# ST_Link.net
KiCad netlist of a schematic drawn in Altium Designer
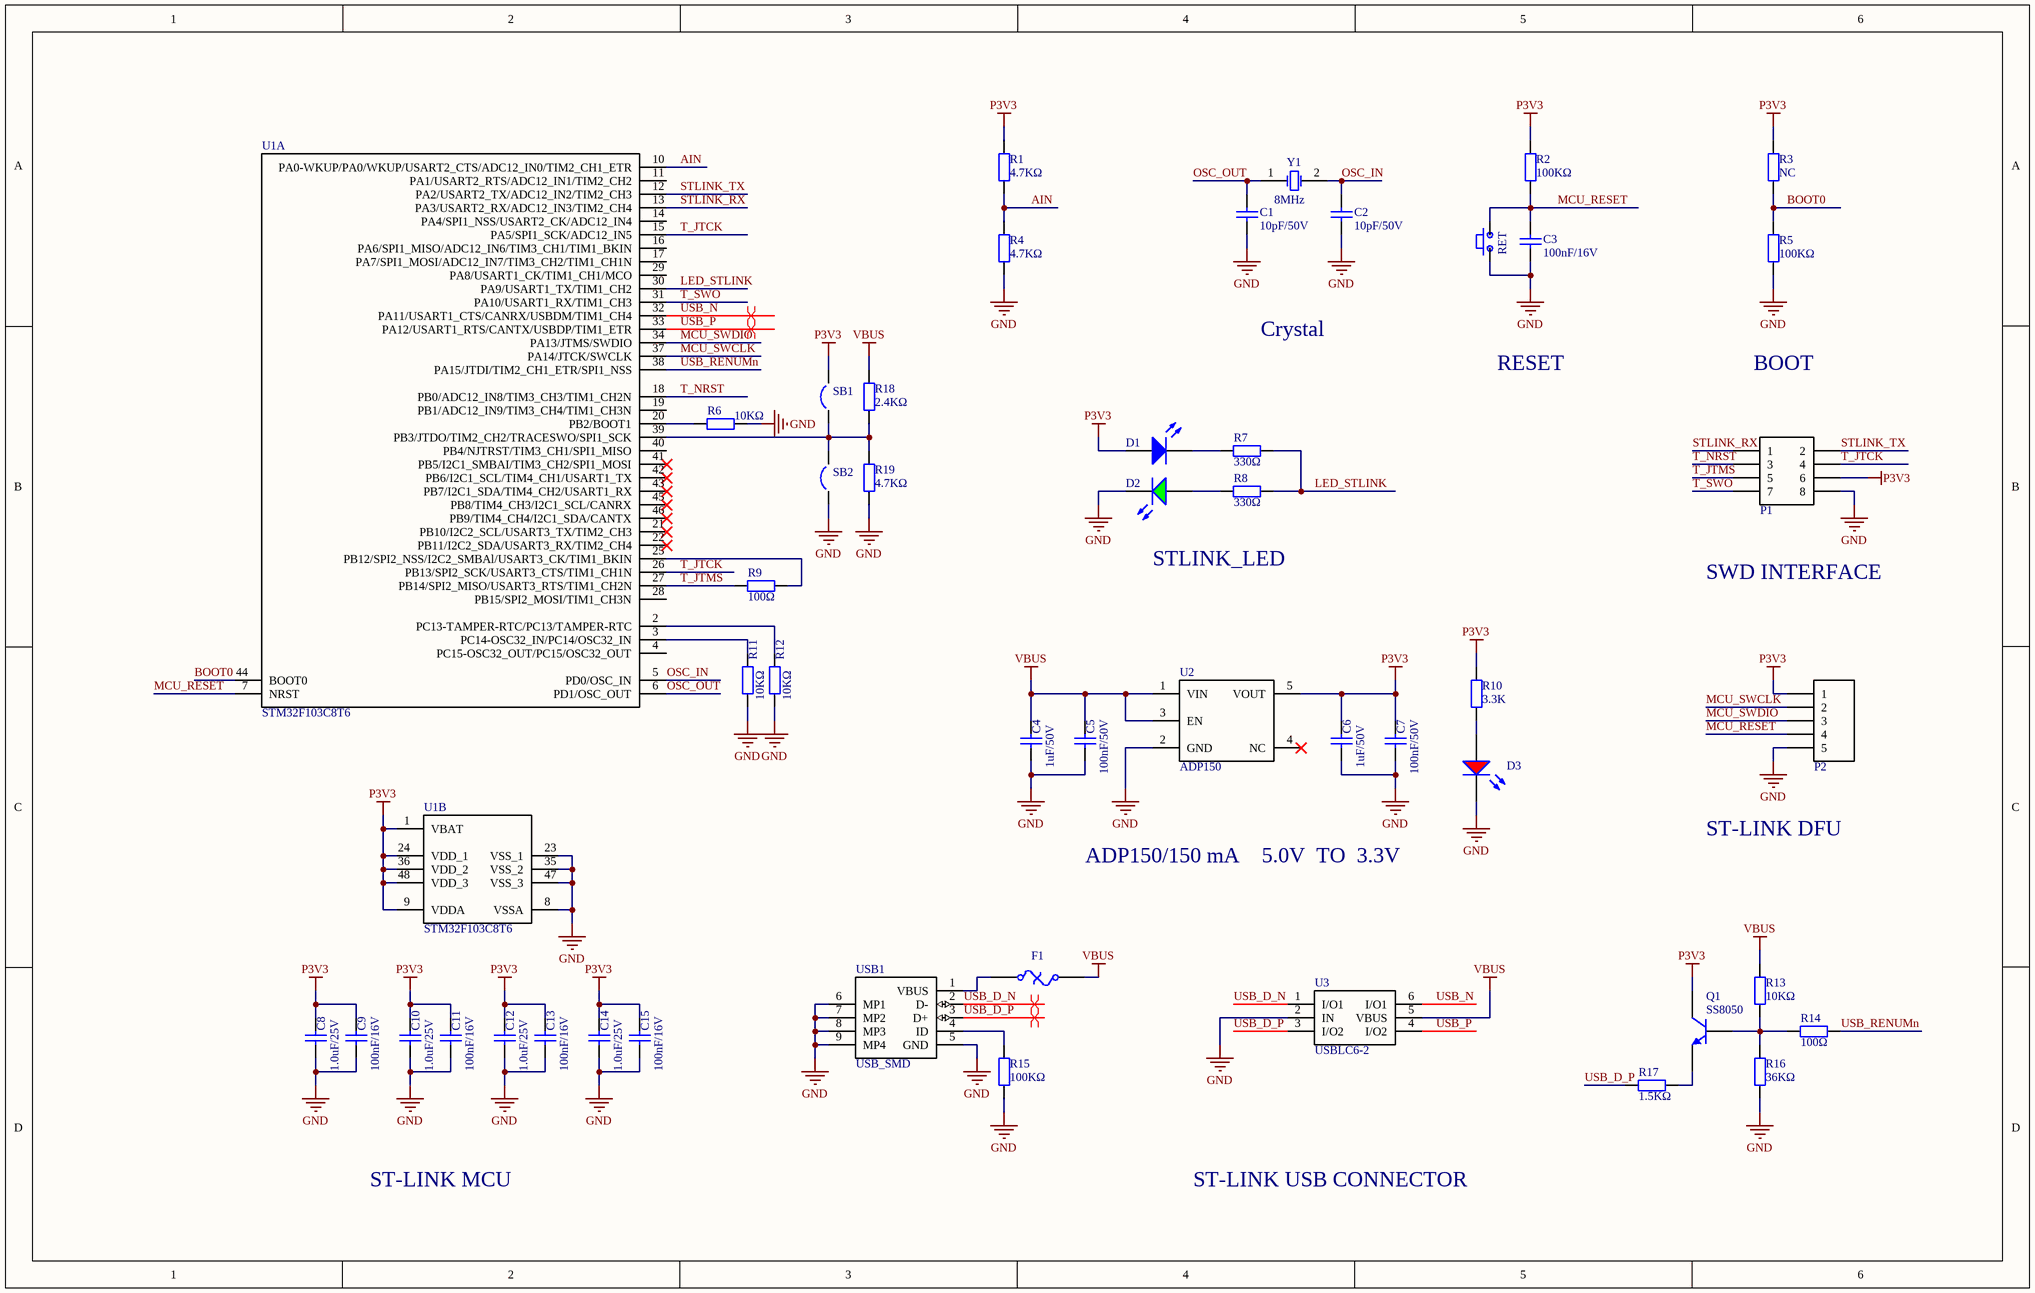
[diagram p0: ST_Link.SchDoc]

(export (version "E")
  (design (tool "Eeschema 10.0.6"))
  (components
    (comp (ref "C1")
      (value "10pF/50V")
      (footprint "0402_C")
      (description "贴片电容")
      (libsource (lib "Miscellaneous Devices LC") (part "0402 10pF (100) 5% 50V"))
    )
    (comp (ref "C2")
      (value "10pF/50V")
      (footprint "0402_C")
      (description "贴片电容")
      (libsource (lib "Miscellaneous Devices LC") (part "0402 10pF (100) 5% 50V"))
    )
    (comp (ref "C3")
      (value "100nF/16V")
      (footprint "0402_C")
      (description "贴片电容")
      (libsource (lib "Miscellaneous Devices LC") (part "0402 100nF (104) 10% 16V"))
    )
    (comp (ref "C4")
      (value "1uF/50V")
      (footprint "0603_C")
      (description "贴片电容")
      (libsource (lib "Miscellaneous Devices LC") (part "0603 1uF (105) 10% 50V"))
    )
    (comp (ref "C5")
      (value "100nF/50V")
      (footprint "0603_C")
      (description "贴片电容")
      (libsource (lib "Miscellaneous Devices LC") (part "0603 100nF (104) 10% 50V"))
    )
    (comp (ref "C6")
      (value "1uF/50V")
      (footprint "0603_C")
      (description "贴片电容")
      (libsource (lib "Miscellaneous Devices LC") (part "0603 1uF (105) 10% 50V"))
    )
    (comp (ref "C7")
      (value "100nF/50V")
      (footprint "0603_C")
      (description "贴片电容")
      (libsource (lib "Miscellaneous Devices LC") (part "0603 100nF (104) 10% 50V"))
    )
    (comp (ref "C8")
      (value "1.0uF/25V")
      (footprint "0402_C")
      (description "贴片电容")
      (libsource (lib "Miscellaneous Devices LC") (part "0402 1.0uF (105) 10% 25V"))
    )
    (comp (ref "C9")
      (value "100nF/16V")
      (footprint "0402_C")
      (description "贴片电容")
      (libsource (lib "Miscellaneous Devices LC") (part "0402 100nF (104) 10% 16V"))
    )
    (comp (ref "C10")
      (value "1.0uF/25V")
      (footprint "0402_C")
      (description "贴片电容")
      (libsource (lib "Miscellaneous Devices LC") (part "0402 1.0uF (105) 10% 25V"))
    )
    (comp (ref "C11")
      (value "100nF/16V")
      (footprint "0402_C")
      (description "贴片电容")
      (libsource (lib "Miscellaneous Devices LC") (part "0402 100nF (104) 10% 16V"))
    )
    (comp (ref "C12")
      (value "1.0uF/25V")
      (footprint "0402_C")
      (description "贴片电容")
      (libsource (lib "Miscellaneous Devices LC") (part "0402 1.0uF (105) 10% 25V"))
    )
    (comp (ref "C13")
      (value "100nF/16V")
      (footprint "0402_C")
      (description "贴片电容")
      (libsource (lib "Miscellaneous Devices LC") (part "0402 100nF (104) 10% 16V"))
    )
    (comp (ref "C14")
      (value "1.0uF/25V")
      (footprint "0402_C")
      (description "贴片电容")
      (libsource (lib "Miscellaneous Devices LC") (part "0402 1.0uF (105) 10% 25V"))
    )
    (comp (ref "C15")
      (value "100nF/16V")
      (footprint "0402_C")
      (description "贴片电容")
      (libsource (lib "Miscellaneous Devices LC") (part "0402 100nF (104) 10% 16V"))
    )
    (comp (ref "D1")
      (value "~")
      (footprint "0603_LED_S1")
      (description "发光二极管")
      (libsource (lib "Miscellaneous Devices LC") (part "0603 蓝灯"))
    )
    (comp (ref "D2")
      (value "~")
      (footprint "0603_LED_S1")
      (description "发光二极管")
      (libsource (lib "Miscellaneous Devices LC") (part "0603 绿灯"))
    )
    (comp (ref "D3")
      (value "红灯 0603")
      (footprint "0603_LED_S1")
      (description "发光二极管")
      (libsource (lib "Miscellaneous Devices LC") (part "0603 红灯"))
    )
    (comp (ref "F1")
      (value "500mA")
      (footprint "F1206")
      (description "Fuse")
      (libsource (lib "Discrete") (part "Fuse"))
    )
    (comp (ref "P1")
      (value "Header")
      (footprint "SMT 2*4 2.54")
      (description "Header, 4-Pin, Dual row")
      (fields (field (name "PUBLISHER") "Altium Limited"))
      (libsource (lib "Connectors") (part "Header 4X2"))
    )
    (comp (ref "P2")
      (value "Header 5")
      (footprint "DIP5_2.00")
      (description "Header, 5-Pin")
      (libsource (lib "Connectors") (part "Header 5"))
    )
    (comp (ref "Q1")
      (value "SS8050")
      (footprint "SOT-23(SOT-23-3)")
      (description "三极管")
      (libsource (lib "Miscellaneous Devices LC") (part "SOT-23 SS8050 Y1"))
    )
    (comp (ref "R1")
      (value "4.7KΩ")
      (footprint "0402_R")
      (description "贴片电阻")
      (libsource (lib "Miscellaneous Devices LC") (part "0402 4.7KΩ (4701) 1%"))
    )
    (comp (ref "R2")
      (value "100KΩ")
      (footprint "0402_R")
      (description "贴片电阻")
      (libsource (lib "Miscellaneous Devices LC") (part "0402 100KΩ (1003) 1%"))
    )
    (comp (ref "R3")
      (value "NC")
      (footprint "0402_R")
      (description "贴片电阻")
      (libsource (lib "Miscellaneous Devices LC") (part "0402 10KΩ (1002) 1%"))
    )
    (comp (ref "R4")
      (value "4.7KΩ")
      (footprint "0402_R")
      (description "贴片电阻")
      (libsource (lib "Miscellaneous Devices LC") (part "0402 4.7KΩ (4701) 1%"))
    )
    (comp (ref "R5")
      (value "100KΩ")
      (footprint "0402_R")
      (description "贴片电阻")
      (libsource (lib "Miscellaneous Devices LC") (part "0402 100KΩ (1003) 1%"))
    )
    (comp (ref "R6")
      (value "10KΩ")
      (footprint "0402_R")
      (description "贴片电阻")
      (libsource (lib "") (part "0402 10KΩ (1002) 1%_1"))
    )
    (comp (ref "R7")
      (value "330Ω")
      (footprint "0402_R")
      (description "贴片电阻")
      (libsource (lib "Miscellaneous Devices LC") (part "0402 330Ω (3300) 1%"))
    )
    (comp (ref "R8")
      (value "330Ω")
      (footprint "0402_R")
      (description "贴片电阻")
      (libsource (lib "Miscellaneous Devices LC") (part "0402 330Ω (3300) 1%"))
    )
    (comp (ref "R9")
      (value "100Ω")
      (footprint "0402_R")
      (description "贴片电阻")
      (libsource (lib "Miscellaneous Devices LC") (part "0402 100Ω (1000) 1%"))
    )
    (comp (ref "R10")
      (value "3.3K")
      (footprint "0603_R")
      (description "贴片电阻")
      (libsource (lib "Miscellaneous Devices LC") (part "0603 3.3KΩ (3301) 1%"))
    )
    (comp (ref "R11")
      (value "10KΩ")
      (footprint "0402_R")
      (description "贴片电阻")
      (libsource (lib "Miscellaneous Devices LC") (part "0402 10KΩ (1002) 1%"))
    )
    (comp (ref "R12")
      (value "10KΩ")
      (footprint "0402_R")
      (description "贴片电阻")
      (libsource (lib "Miscellaneous Devices LC") (part "0402 10KΩ (1002) 1%"))
    )
    (comp (ref "R13")
      (value "10KΩ")
      (footprint "0402_R")
      (description "贴片电阻")
      (libsource (lib "Miscellaneous Devices LC") (part "0402 10KΩ (1002) 1%"))
    )
    (comp (ref "R14")
      (value "100Ω")
      (footprint "0402_R")
      (description "贴片电阻")
      (libsource (lib "Miscellaneous Devices LC") (part "0402 100Ω (1000) 1%"))
    )
    (comp (ref "R15")
      (value "100KΩ")
      (footprint "0402_R")
      (description "贴片电阻")
      (libsource (lib "Miscellaneous Devices LC") (part "0402 100KΩ (1003) 1%"))
    )
    (comp (ref "R16")
      (value "36KΩ")
      (footprint "0402_R")
      (description "贴片电阻")
      (libsource (lib "Miscellaneous Devices LC") (part "0402 39KΩ (3902) 1%"))
    )
    (comp (ref "R17")
      (value "1.5KΩ")
      (footprint "0402_R")
      (description "贴片电阻")
      (libsource (lib "Miscellaneous Devices LC") (part "0402 1.5KΩ (1501) 1%"))
    )
    (comp (ref "R18")
      (value "2.4KΩ")
      (footprint "0402_R")
      (description "贴片电阻")
      (libsource (lib "Miscellaneous Devices LC") (part "0402 2.4KΩ (2401) 1%"))
    )
    (comp (ref "R19")
      (value "4.7KΩ")
      (footprint "0402_R")
      (description "贴片电阻")
      (libsource (lib "Miscellaneous Devices LC") (part "0402 4.7KΩ (4701) 1%"))
    )
    (comp (ref "RET")
      (value "Button")
      (footprint "SKRKAHE020")
      (libsource (lib "Connectors") (part "Button"))
    )
    (comp (ref "SB1") (value "SB") (footprint "SB") (libsource (lib "Connectors") (part "SB")))
    (comp (ref "SB2") (value "SB") (footprint "SB") (libsource (lib "") (part "SB_1")))
    (comp (ref "U1")
      (value "STM32F103C8T6")
      (footprint "LQFP-48")
      (libsource (lib "IC") (part "STM32F103C8T6"))
    )
    (comp (ref "U2")
      (value "ADP150")
      (footprint "SOT23-5")
      (description "Ultralow Noise,150 mA CMOS Linear Regulator")
      (libsource (lib "IC") (part "ADP150"))
    )
    (comp (ref "U3")
      (value "USBLC6-2")
      (footprint "SOT23-6")
      (description "Very low capacitance ESD protection")
      (libsource (lib "IC") (part "USBLC6-2"))
    )
    (comp (ref "USB1")
      (value "USB_SMD")
      (footprint "USB_Micro")
      (libsource (lib "Connectors") (part "USB_SMD"))
    )
    (comp (ref "Y1")
      (value "8MHz")
      (footprint "SMD-5032_2P")
      (description "贴片晶振")
      (libsource (lib "Miscellaneous Devices LC") (part "SMD-5032_2P 8MHz 20ppm 20pF"))
    )
  )
  (nets
    (net (code "1") (name "/AIN") (class "Default")
      (node (ref "R1") (pin "1") (pinfunction "1_1") (pintype "passive"))
      (node (ref "R4") (pin "2") (pinfunction "2_2") (pintype "passive"))
      (node (ref "U1") (pin "10") (pinfunction "PA0-WKUP/PA0/WKUP/USART2_CTS/ADC12_IN0/TIM2_CH1_ETR_10") (pintype "passive"))
    )
    (net (code "2") (name "/BOOT0") (class "Default")
      (node (ref "R3") (pin "1") (pinfunction "1_1") (pintype "passive"))
      (node (ref "R5") (pin "2") (pinfunction "2_2") (pintype "passive"))
      (node (ref "U1") (pin "44") (pinfunction "BOOT0_44") (pintype "passive"))
    )
    (net (code "3") (name "/LED_STLINK") (class "Default")
      (node (ref "R7") (pin "2") (pinfunction "2_2") (pintype "passive"))
      (node (ref "R8") (pin "2") (pinfunction "2_2") (pintype "passive"))
      (node (ref "U1") (pin "30") (pinfunction "PA9/USART1_TX/TIM1_CH2_30") (pintype "passive"))
    )
    (net (code "4") (name "/MCU_RESET") (class "Default")
      (node (ref "C3") (pin "2") (pinfunction "2_2") (pintype "passive"))
      (node (ref "P2") (pin "4") (pinfunction "4_4") (pintype "passive"))
      (node (ref "R2") (pin "1") (pinfunction "1_1") (pintype "passive"))
      (node (ref "RET") (pin "2") (pinfunction "2_2") (pintype "passive"))
      (node (ref "U1") (pin "7") (pinfunction "NRST_7") (pintype "passive"))
    )
    (net (code "5") (name "/MCU_SWCLK") (class "Default")
      (node (ref "P2") (pin "2") (pinfunction "2_2") (pintype "passive"))
      (node (ref "U1") (pin "37") (pinfunction "PA14/JTCK/SWCLK_37") (pintype "passive"))
    )
    (net (code "6") (name "/MCU_SWDIO") (class "Default")
      (node (ref "P2") (pin "3") (pinfunction "3_3") (pintype "passive"))
      (node (ref "U1") (pin "34") (pinfunction "PA13/JTMS/SWDIO_34") (pintype "passive"))
    )
    (net (code "7") (name "/OSC_IN") (class "Default")
      (node (ref "C2") (pin "2") (pinfunction "2_2") (pintype "passive"))
      (node (ref "U1") (pin "5") (pinfunction "PD0/OSC_IN_5") (pintype "passive"))
      (node (ref "Y1") (pin "2") (pinfunction "OSC2_2") (pintype "passive"))
    )
    (net (code "8") (name "/OSC_OUT") (class "Default")
      (node (ref "C1") (pin "2") (pinfunction "2_2") (pintype "passive"))
      (node (ref "U1") (pin "6") (pinfunction "PD1/OSC_OUT_6") (pintype "passive"))
      (node (ref "Y1") (pin "1") (pinfunction "OSC1_1") (pintype "passive"))
    )
    (net (code "9") (name "/STLINK_RX") (class "Default")
      (node (ref "P1") (pin "1") (pinfunction "1_1") (pintype "passive"))
      (node (ref "U1") (pin "13") (pinfunction "PA3/USART2_RX/ADC12_IN3/TIM2_CH4_13") (pintype "passive"))
    )
    (net (code "10") (name "/STLINK_TX") (class "Default")
      (node (ref "P1") (pin "2") (pinfunction "2_2") (pintype "passive"))
      (node (ref "U1") (pin "12") (pinfunction "PA2/USART2_TX/ADC12_IN2/TIM2_CH3_12") (pintype "passive"))
    )
    (net (code "11") (name "/T_JTCK") (class "Default")
      (node (ref "P1") (pin "4") (pinfunction "4_4") (pintype "passive"))
      (node (ref "U1") (pin "15") (pinfunction "PA5/SPI1_SCK/ADC12_IN5_15") (pintype "passive"))
      (node (ref "U1") (pin "26") (pinfunction "PB13/SPI2_SCK/USART3_CTS/TIM1_CH1N_26") (pintype "passive"))
    )
    (net (code "12") (name "/T_JTMS") (class "Default")
      (node (ref "P1") (pin "5") (pinfunction "5_5") (pintype "passive"))
      (node (ref "R9") (pin "1") (pinfunction "1_1") (pintype "passive"))
      (node (ref "U1") (pin "27") (pinfunction "PB14/SPI2_MISO/USART3_RTS/TIM1_CH2N_27") (pintype "passive"))
    )
    (net (code "13") (name "/T_NRST") (class "Default")
      (node (ref "P1") (pin "3") (pinfunction "3_3") (pintype "passive"))
      (node (ref "U1") (pin "18") (pinfunction "PB0/ADC12_IN8/TIM3_CH3/TIM1_CH2N_18") (pintype "passive"))
    )
    (net (code "14") (name "/T_SWO") (class "Default")
      (node (ref "P1") (pin "7") (pinfunction "7_7") (pintype "passive"))
      (node (ref "U1") (pin "31") (pinfunction "PA10/USART1_RX/TIM1_CH3_31") (pintype "passive"))
    )
    (net (code "15") (name "/USB_D_N") (class "Default")
      (node (ref "U3") (pin "1") (pinfunction "I/O1_1") (pintype "passive"))
      (node (ref "USB1") (pin "2") (pinfunction "D-_2") (pintype "bidirectional"))
    )
    (net (code "16") (name "/USB_D_P") (class "Default")
      (node (ref "R17") (pin "1") (pinfunction "1_1") (pintype "passive"))
      (node (ref "U3") (pin "3") (pinfunction "I/O2_3") (pintype "passive"))
      (node (ref "USB1") (pin "3") (pinfunction "D+_3") (pintype "bidirectional"))
    )
    (net (code "17") (name "/USB_N") (class "Default")
      (node (ref "U1") (pin "32") (pinfunction "PA11/USART1_CTS/CANRX/USBDM/TIM1_CH4_32") (pintype "passive"))
      (node (ref "U3") (pin "6") (pinfunction "I/O1_6") (pintype "passive"))
    )
    (net (code "18") (name "/USB_P") (class "Default")
      (node (ref "U1") (pin "33") (pinfunction "PA12/USART1_RTS/CANTX/USBDP/TIM1_ETR_33") (pintype "passive"))
      (node (ref "U3") (pin "4") (pinfunction "I/O2_4") (pintype "passive"))
    )
    (net (code "19") (name "/USB_RENUMn") (class "Default")
      (node (ref "R14") (pin "2") (pinfunction "2_2") (pintype "passive"))
      (node (ref "U1") (pin "38") (pinfunction "PA15/JTDI/TIM2_CH1_ETR/SPI1_NSS_38") (pintype "passive"))
    )
    (net (code "20") (name "GND") (class "Default")
      (node (ref "C1") (pin "1") (pinfunction "1_1") (pintype "passive"))
      (node (ref "C10") (pin "1") (pinfunction "1_1") (pintype "passive"))
      (node (ref "C11") (pin "1") (pinfunction "1_1") (pintype "passive"))
      (node (ref "C12") (pin "1") (pinfunction "1_1") (pintype "passive"))
      (node (ref "C13") (pin "1") (pinfunction "1_1") (pintype "passive"))
      (node (ref "C14") (pin "1") (pinfunction "1_1") (pintype "passive"))
      (node (ref "C15") (pin "1") (pinfunction "1_1") (pintype "passive"))
      (node (ref "C2") (pin "1") (pinfunction "1_1") (pintype "passive"))
      (node (ref "C3") (pin "1") (pinfunction "1_1") (pintype "passive"))
      (node (ref "C4") (pin "1") (pinfunction "1_1") (pintype "passive"))
      (node (ref "C5") (pin "1") (pinfunction "1_1") (pintype "passive"))
      (node (ref "C6") (pin "1") (pinfunction "1_1") (pintype "passive"))
      (node (ref "C7") (pin "1") (pinfunction "1_1") (pintype "passive"))
      (node (ref "C8") (pin "1") (pinfunction "1_1") (pintype "passive"))
      (node (ref "C9") (pin "1") (pinfunction "1_1") (pintype "passive"))
      (node (ref "D2") (pin "K") (pinfunction "K_K") (pintype "passive"))
      (node (ref "D3") (pin "K") (pinfunction "K_K") (pintype "passive"))
      (node (ref "P1") (pin "8") (pinfunction "8_8") (pintype "passive"))
      (node (ref "P2") (pin "5") (pinfunction "5_5") (pintype "passive"))
      (node (ref "R11") (pin "1") (pinfunction "1_1") (pintype "passive"))
      (node (ref "R12") (pin "1") (pinfunction "1_1") (pintype "passive"))
      (node (ref "R15") (pin "1") (pinfunction "1_1") (pintype "passive"))
      (node (ref "R16") (pin "1") (pinfunction "1_1") (pintype "passive"))
      (node (ref "R19") (pin "1") (pinfunction "1_1") (pintype "passive"))
      (node (ref "R4") (pin "1") (pinfunction "1_1") (pintype "passive"))
      (node (ref "R5") (pin "1") (pinfunction "1_1") (pintype "passive"))
      (node (ref "R6") (pin "1") (pinfunction "1_1") (pintype "passive"))
      (node (ref "RET") (pin "1") (pinfunction "1_1") (pintype "passive"))
      (node (ref "SB2") (pin "2") (pinfunction "2_2") (pintype "passive"))
      (node (ref "U1") (pin "23") (pinfunction "VSS_1_23") (pintype "power_in"))
      (node (ref "U1") (pin "35") (pinfunction "VSS_2_35") (pintype "power_in"))
      (node (ref "U1") (pin "47") (pinfunction "VSS_3_47") (pintype "power_in"))
      (node (ref "U1") (pin "8") (pinfunction "VSSA_8") (pintype "power_in"))
      (node (ref "U2") (pin "2") (pinfunction "GND_2") (pintype "passive"))
      (node (ref "U3") (pin "2") (pinfunction "IN_2") (pintype "passive"))
      (node (ref "USB1") (pin "5") (pinfunction "GND_5") (pintype "power_in"))
      (node (ref "USB1") (pin "6") (pinfunction "MP1_6") (pintype "passive"))
      (node (ref "USB1") (pin "7") (pinfunction "MP2_7") (pintype "passive"))
      (node (ref "USB1") (pin "8") (pinfunction "MP3_8") (pintype "passive"))
      (node (ref "USB1") (pin "9") (pinfunction "MP4_9") (pintype "passive"))
    )
    (net (code "21") (name "Net-(D1-PadK)") (class "Default")
      (node (ref "D1") (pin "K") (pinfunction "K_K") (pintype "passive"))
      (node (ref "R7") (pin "1") (pinfunction "1_1") (pintype "passive"))
    )
    (net (code "22") (name "Net-(D2-PadA)") (class "Default")
      (node (ref "D2") (pin "A") (pinfunction "A_A") (pintype "passive"))
      (node (ref "R8") (pin "1") (pinfunction "1_1") (pintype "passive"))
    )
    (net (code "23") (name "Net-(D3-PadA)") (class "Default")
      (node (ref "D3") (pin "A") (pinfunction "A_A") (pintype "passive"))
      (node (ref "R10") (pin "1") (pinfunction "1_1") (pintype "passive"))
    )
    (net (code "24") (name "Net-(Q1-B)") (class "Default")
      (node (ref "Q1") (pin "1") (pinfunction "B_1") (pintype "passive"))
      (node (ref "R13") (pin "1") (pinfunction "1_1") (pintype "passive"))
      (node (ref "R14") (pin "1") (pinfunction "1_1") (pintype "passive"))
      (node (ref "R16") (pin "2") (pinfunction "2_2") (pintype "passive"))
    )
    (net (code "25") (name "Net-(Q1-E)") (class "Default")
      (node (ref "Q1") (pin "2") (pinfunction "E_2") (pintype "passive"))
      (node (ref "R17") (pin "2") (pinfunction "2_2") (pintype "passive"))
    )
    (net (code "26") (name "Net-(U1A-PB2{slash}BOOT1)") (class "Default")
      (node (ref "R6") (pin "2") (pinfunction "2_2") (pintype "passive"))
      (node (ref "U1") (pin "20") (pinfunction "PB2/BOOT1_20") (pintype "passive"))
    )
    (net (code "27") (name "Net-(U1A-PB3{slash}JTDO{slash}TIM2_CH2{slash}TRACESWO{slash}SPI1_SCK)") (class "Default")
      (node (ref "R18") (pin "1") (pinfunction "1_1") (pintype "passive"))
      (node (ref "R19") (pin "2") (pinfunction "2_2") (pintype "passive"))
      (node (ref "SB1") (pin "1") (pinfunction "1_1") (pintype "passive"))
      (node (ref "SB2") (pin "1") (pinfunction "1_1") (pintype "passive"))
      (node (ref "U1") (pin "39") (pinfunction "PB3/JTDO/TIM2_CH2/TRACESWO/SPI1_SCK_39") (pintype "passive"))
    )
    (net (code "28") (name "Net-(U1A-PB12{slash}SPI2_NSS{slash}I2C2_SMBAl{slash}USART3_CK{slash}TIM1_BKIN)") (class "Default")
      (node (ref "R9") (pin "2") (pinfunction "2_2") (pintype "passive"))
      (node (ref "U1") (pin "25") (pinfunction "PB12/SPI2_NSS/I2C2_SMBAl/USART3_CK/TIM1_BKIN_25") (pintype "passive"))
    )
    (net (code "29") (name "Net-(U1A-PC13-TAMPER-RTC{slash}PC13{slash}TAMPER-RTC)") (class "Default")
      (node (ref "R12") (pin "2") (pinfunction "2_2") (pintype "passive"))
      (node (ref "U1") (pin "2") (pinfunction "PC13-TAMPER-RTC/PC13/TAMPER-RTC_2") (pintype "passive"))
    )
    (net (code "30") (name "Net-(U1A-PC14-OSC32_IN{slash}PC14{slash}OSC32_IN)") (class "Default")
      (node (ref "R11") (pin "2") (pinfunction "2_2") (pintype "passive"))
      (node (ref "U1") (pin "3") (pinfunction "PC14-OSC32_IN/PC14/OSC32_IN_3") (pintype "passive"))
    )
    (net (code "31") (name "Net-(USB1-ID)") (class "Default")
      (node (ref "R15") (pin "2") (pinfunction "2_2") (pintype "passive"))
      (node (ref "USB1") (pin "4") (pinfunction "ID_4") (pintype "passive"))
    )
    (net (code "32") (name "Net-(USB1-VBUS)") (class "Default")
      (node (ref "F1") (pin "1") (pinfunction "1_1") (pintype "passive"))
      (node (ref "USB1") (pin "1") (pinfunction "VBUS_1") (pintype "power_in"))
    )
    (net (code "33") (name "P3V3") (class "Default")
      (node (ref "C10") (pin "2") (pinfunction "2_2") (pintype "passive"))
      (node (ref "C11") (pin "2") (pinfunction "2_2") (pintype "passive"))
      (node (ref "C12") (pin "2") (pinfunction "2_2") (pintype "passive"))
      (node (ref "C13") (pin "2") (pinfunction "2_2") (pintype "passive"))
      (node (ref "C14") (pin "2") (pinfunction "2_2") (pintype "passive"))
      (node (ref "C15") (pin "2") (pinfunction "2_2") (pintype "passive"))
      (node (ref "C6") (pin "2") (pinfunction "2_2") (pintype "passive"))
      (node (ref "C7") (pin "2") (pinfunction "2_2") (pintype "passive"))
      (node (ref "C8") (pin "2") (pinfunction "2_2") (pintype "passive"))
      (node (ref "C9") (pin "2") (pinfunction "2_2") (pintype "passive"))
      (node (ref "D1") (pin "A") (pinfunction "A_A") (pintype "passive"))
      (node (ref "P1") (pin "6") (pinfunction "6_6") (pintype "passive"))
      (node (ref "P2") (pin "1") (pinfunction "1_1") (pintype "passive"))
      (node (ref "Q1") (pin "3") (pinfunction "C_3") (pintype "passive"))
      (node (ref "R1") (pin "2") (pinfunction "2_2") (pintype "passive"))
      (node (ref "R10") (pin "2") (pinfunction "2_2") (pintype "passive"))
      (node (ref "R2") (pin "2") (pinfunction "2_2") (pintype "passive"))
      (node (ref "R3") (pin "2") (pinfunction "2_2") (pintype "passive"))
      (node (ref "SB1") (pin "2") (pinfunction "2_2") (pintype "passive"))
      (node (ref "U1") (pin "1") (pinfunction "VBAT_1") (pintype "power_in"))
      (node (ref "U1") (pin "24") (pinfunction "VDD_1_24") (pintype "power_in"))
      (node (ref "U1") (pin "36") (pinfunction "VDD_2_36") (pintype "power_in"))
      (node (ref "U1") (pin "48") (pinfunction "VDD_3_48") (pintype "power_in"))
      (node (ref "U1") (pin "9") (pinfunction "VDDA_9") (pintype "power_in"))
      (node (ref "U2") (pin "5") (pinfunction "VOUT_5") (pintype "passive"))
    )
    (net (code "34") (name "VBUS") (class "Default")
      (node (ref "C4") (pin "2") (pinfunction "2_2") (pintype "passive"))
      (node (ref "C5") (pin "2") (pinfunction "2_2") (pintype "passive"))
      (node (ref "F1") (pin "2") (pinfunction "2_2") (pintype "passive"))
      (node (ref "R13") (pin "2") (pinfunction "2_2") (pintype "passive"))
      (node (ref "R18") (pin "2") (pinfunction "2_2") (pintype "passive"))
      (node (ref "U2") (pin "1") (pinfunction "VIN_1") (pintype "passive"))
      (node (ref "U2") (pin "3") (pinfunction "EN_3") (pintype "passive"))
      (node (ref "U3") (pin "5") (pinfunction "VBUS_5") (pintype "passive"))
    )
    (net (code "35") (name "unconnected-(U1A-PA1{slash}USART2_RTS{slash}ADC12_IN1{slash}TIM2_CH2-Pad11)") (class "Default")
      (node (ref "U1") (pin "11") (pinfunction "PA1/USART2_RTS/ADC12_IN1/TIM2_CH2_11") (pintype "passive"))
    )
    (net (code "36") (name "unconnected-(U1A-PA4{slash}SPI1_NSS{slash}USART2_CK{slash}ADC12_IN4-Pad14)") (class "Default")
      (node (ref "U1") (pin "14") (pinfunction "PA4/SPI1_NSS/USART2_CK/ADC12_IN4_14") (pintype "passive"))
    )
    (net (code "37") (name "unconnected-(U1A-PA6{slash}SPI1_MISO{slash}ADC12_IN6{slash}TIM3_CH1{slash}TIM1_BKIN-Pad16)") (class "Default")
      (node (ref "U1") (pin "16") (pinfunction "PA6/SPI1_MISO/ADC12_IN6/TIM3_CH1/TIM1_BKIN_16") (pintype "passive"))
    )
    (net (code "38") (name "unconnected-(U1A-PA7{slash}SPI1_MOSI{slash}ADC12_IN7{slash}TIM3_CH2{slash}TIM1_CH1N-Pad17)") (class "Default")
      (node (ref "U1") (pin "17") (pinfunction "PA7/SPI1_MOSI/ADC12_IN7/TIM3_CH2/TIM1_CH1N_17") (pintype "passive"))
    )
    (net (code "39") (name "unconnected-(U1A-PA8{slash}USART1_CK{slash}TIM1_CH1{slash}MCO-Pad29)") (class "Default")
      (node (ref "U1") (pin "29") (pinfunction "PA8/USART1_CK/TIM1_CH1/MCO_29") (pintype "passive"))
    )
    (net (code "40") (name "unconnected-(U1A-PB1{slash}ADC12_IN9{slash}TIM3_CH4{slash}TIM1_CH3N-Pad19)") (class "Default")
      (node (ref "U1") (pin "19") (pinfunction "PB1/ADC12_IN9/TIM3_CH4/TIM1_CH3N_19") (pintype "passive"))
    )
    (net (code "41") (name "unconnected-(U1A-PB4{slash}NJTRST{slash}TIM3_CH1{slash}SPI1_MISO-Pad40)") (class "Default")
      (node (ref "U1") (pin "40") (pinfunction "PB4/NJTRST/TIM3_CH1/SPI1_MISO_40") (pintype "passive"))
    )
    (net (code "42") (name "unconnected-(U1A-PB5{slash}I2C1_SMBAI{slash}TIM3_CH2{slash}SPI1_MOSI-Pad41)") (class "Default")
      (node (ref "U1") (pin "41") (pinfunction "PB5/I2C1_SMBAI/TIM3_CH2/SPI1_MOSI_41") (pintype "passive+no_connect"))
    )
    (net (code "43") (name "unconnected-(U1A-PB6{slash}I2C1_SCL{slash}TIM4_CH1{slash}USART1_TX-Pad42)") (class "Default")
      (node (ref "U1") (pin "42") (pinfunction "PB6/I2C1_SCL/TIM4_CH1/USART1_TX_42") (pintype "passive+no_connect"))
    )
    (net (code "44") (name "unconnected-(U1A-PB7{slash}I2C1_SDA{slash}TIM4_CH2{slash}USART1_RX-Pad43)") (class "Default")
      (node (ref "U1") (pin "43") (pinfunction "PB7/I2C1_SDA/TIM4_CH2/USART1_RX_43") (pintype "passive+no_connect"))
    )
    (net (code "45") (name "unconnected-(U1A-PB8{slash}TIM4_CH3{slash}I2C1_SCL{slash}CANRX-Pad45)") (class "Default")
      (node (ref "U1") (pin "45") (pinfunction "PB8/TIM4_CH3/I2C1_SCL/CANRX_45") (pintype "passive+no_connect"))
    )
    (net (code "46") (name "unconnected-(U1A-PB9{slash}TIM4_CH4{slash}I2C1_SDA{slash}CANTX-Pad46)") (class "Default")
      (node (ref "U1") (pin "46") (pinfunction "PB9/TIM4_CH4/I2C1_SDA/CANTX_46") (pintype "passive+no_connect"))
    )
    (net (code "47") (name "unconnected-(U1A-PB10{slash}I2C2_SCL{slash}USART3_TX{slash}TIM2_CH3-Pad21)") (class "Default")
      (node (ref "U1") (pin "21") (pinfunction "PB10/I2C2_SCL/USART3_TX/TIM2_CH3_21") (pintype "passive+no_connect"))
    )
    (net (code "48") (name "unconnected-(U1A-PB11{slash}I2C2_SDA{slash}USART3_RX{slash}TIM2_CH4-Pad22)") (class "Default")
      (node (ref "U1") (pin "22") (pinfunction "PB11/I2C2_SDA/USART3_RX/TIM2_CH4_22") (pintype "passive+no_connect"))
    )
    (net (code "49") (name "unconnected-(U1A-PB15{slash}SPI2_MOSI{slash}TIM1_CH3N-Pad28)") (class "Default")
      (node (ref "U1") (pin "28") (pinfunction "PB15/SPI2_MOSI/TIM1_CH3N_28") (pintype "passive"))
    )
    (net (code "50") (name "unconnected-(U1A-PC15-OSC32_OUT{slash}PC15{slash}OSC32_OUT-Pad4)") (class "Default")
      (node (ref "U1") (pin "4") (pinfunction "PC15-OSC32_OUT/PC15/OSC32_OUT_4") (pintype "passive"))
    )
    (net (code "51") (name "unconnected-(U2-NC-Pad4)") (class "Default")
      (node (ref "U2") (pin "4") (pinfunction "NC_4") (pintype "passive+no_connect"))
    )
  )
)
